# X8-Navboard.net
KiCad netlist of a schematic drawn in EAGLE
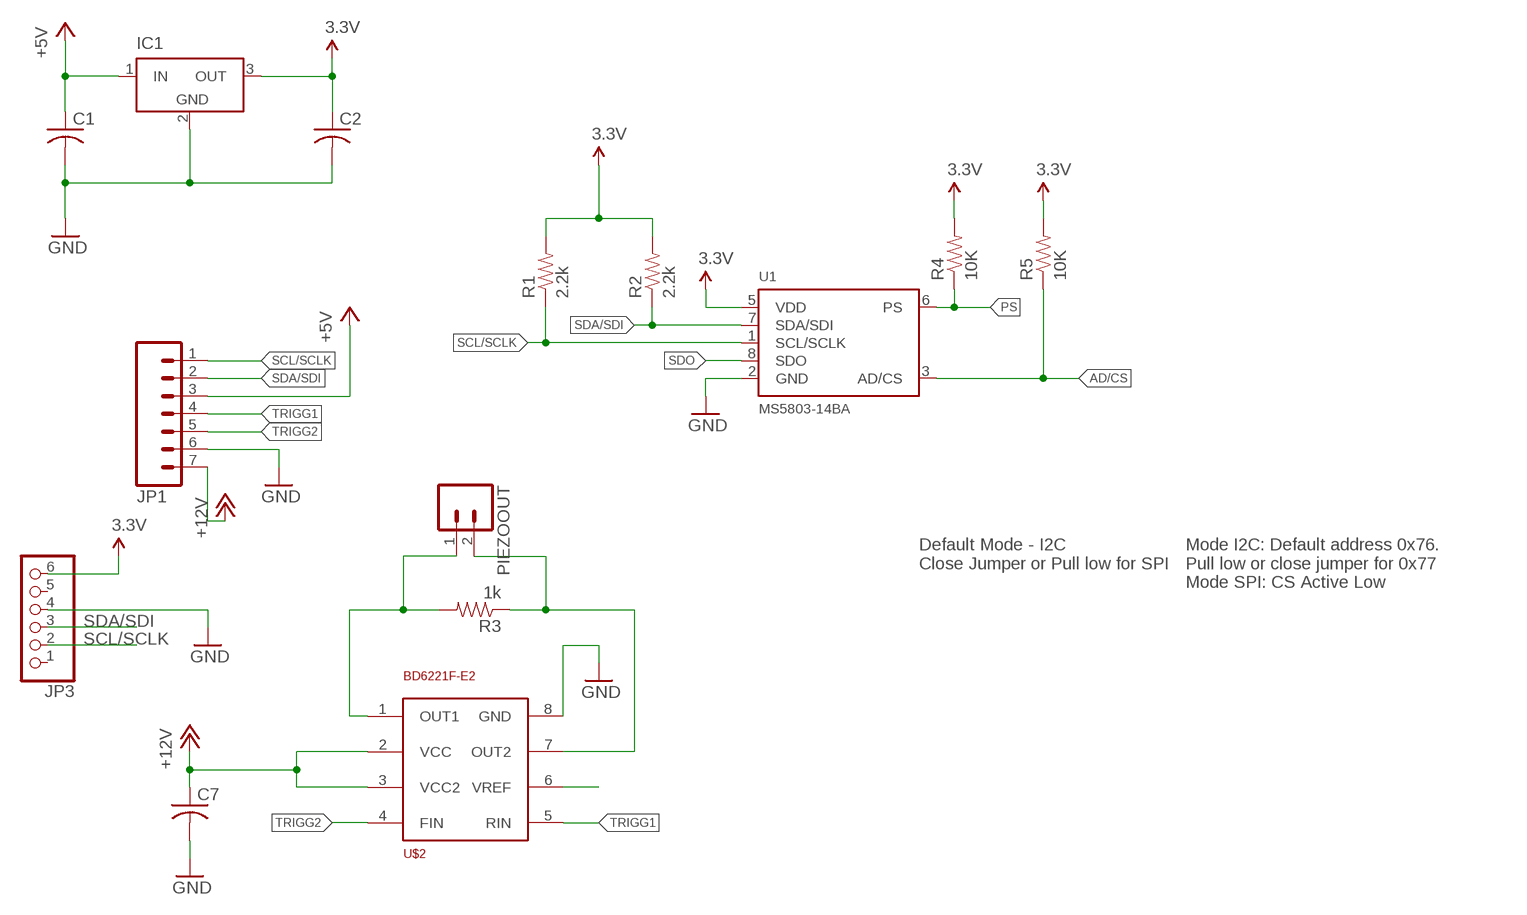
[diagram p0: schematic, sheet 1]

(export (version "E")
  (design (tool "Eeschema 10.0.6"))
  (components
    (comp (ref "C1")
      (value "C-USC0603")
      (footprint "eagle-import:C0603")
      (libsource (lib "eagle-import") (part "C-USC0603"))
    )
    (comp (ref "C2")
      (value "C-USC0603")
      (footprint "eagle-import:C0603")
      (libsource (lib "eagle-import") (part "C-USC0603"))
    )
    (comp (ref "C7")
      (value "C-USC0603")
      (footprint "eagle-import:C0603")
      (libsource (lib "eagle-import") (part "C-USC0603"))
    )
    (comp (ref "IC1")
      (value "LT1129CST5")
      (footprint "eagle-import:SOT223")
      (fields (field (name "MPN") "LT1129CST-5#PBF"))
      (libsource (lib "eagle-import") (part "LT1129CST5"))
    )
    (comp (ref "JP1")
      (value "M07")
      (footprint "eagle-import:1X07")
      (libsource (lib "eagle-import") (part "M07"))
    )
    (comp (ref "JP3")
      (value "PINHD-1X6")
      (footprint "eagle-import:1X06")
      (libsource (lib "eagle-import") (part "PINHD-1X6"))
    )
    (comp (ref "PIEZOOUT")
      (value "M02LOCK_LONGPADS")
      (footprint "eagle-import:1X02_LOCK_LONGPADS")
      (libsource (lib "eagle-import") (part "M02LOCK_LONGPADS"))
    )
    (comp (ref "R1")
      (value "2.2k")
      (footprint "eagle-import:0603-RES")
      (libsource (lib "eagle-import") (part "2.2KOHM1/10W1%(0603)"))
    )
    (comp (ref "R2")
      (value "2.2k")
      (footprint "eagle-import:0603-RES")
      (libsource (lib "eagle-import") (part "2.2KOHM1/10W1%(0603)"))
    )
    (comp (ref "R3")
      (value "1k")
      (footprint "eagle-import:0603-RES")
      (libsource (lib "eagle-import") (part "2.2KOHM1/10W1%(0603)"))
    )
    (comp (ref "R4")
      (value "10K")
      (footprint "eagle-import:0603-RES")
      (libsource (lib "eagle-import") (part "10KOHM1/10W1%(0603)0603"))
    )
    (comp (ref "R5")
      (value "10K")
      (footprint "eagle-import:0603-RES")
      (libsource (lib "eagle-import") (part "10KOHM1/10W1%(0603)0603"))
    )
    (comp (ref "U$2")
      (value "BD6221F-E2")
      (footprint "eagle-import:SOIC8")
      (libsource (lib "eagle-import") (part "BD6221F-E2"))
    )
    (comp (ref "U1")
      (value "MS5803-14BA")
      (footprint "eagle-import:MS5803")
      (libsource (lib "eagle-import") (part "MS5803-14BA"))
    )
  )
  (nets
    (net (code "1") (name "+5V") (class "Default")
      (node (ref "C1") (pin "1") (pinfunction "1_1") (pintype "passive"))
      (node (ref "IC1") (pin "1") (pinfunction "IN_1") (pintype "input"))
      (node (ref "JP1") (pin "3") (pinfunction "3_3") (pintype "passive"))
    )
    (net (code "2") (name "+12V") (class "Default")
      (node (ref "C7") (pin "1") (pinfunction "1_1") (pintype "passive"))
      (node (ref "JP1") (pin "7") (pinfunction "7_7") (pintype "passive"))
      (node (ref "U$2") (pin "2") (pinfunction "VCC_2") (pintype "bidirectional"))
      (node (ref "U$2") (pin "3") (pinfunction "VCC2_3") (pintype "bidirectional"))
    )
    (net (code "3") (name "3.3V") (class "Default")
      (node (ref "C2") (pin "1") (pinfunction "1_1") (pintype "passive"))
      (node (ref "IC1") (pin "3") (pinfunction "OUT_3") (pintype "output"))
      (node (ref "JP3") (pin "6") (pinfunction "6_6") (pintype "passive"))
      (node (ref "R1") (pin "2") (pinfunction "2_2") (pintype "passive"))
      (node (ref "R2") (pin "2") (pinfunction "2_2") (pintype "passive"))
      (node (ref "R4") (pin "2") (pinfunction "2_2") (pintype "passive"))
      (node (ref "R5") (pin "2") (pinfunction "2_2") (pintype "passive"))
      (node (ref "U1") (pin "5") (pinfunction "VDD_5") (pintype "bidirectional"))
    )
    (net (code "4") (name "AD{slash}CS") (class "Default")
      (node (ref "R5") (pin "1") (pinfunction "1_1") (pintype "passive"))
      (node (ref "U1") (pin "3") (pinfunction "AD/CS_3") (pintype "bidirectional"))
    )
    (net (code "5") (name "GND") (class "Default")
      (node (ref "C1") (pin "2") (pinfunction "2_2") (pintype "passive"))
      (node (ref "C2") (pin "2") (pinfunction "2_2") (pintype "passive"))
      (node (ref "C7") (pin "2") (pinfunction "2_2") (pintype "passive"))
      (node (ref "IC1") (pin "2") (pinfunction "GND_2") (pintype "power_in"))
      (node (ref "JP1") (pin "6") (pinfunction "6_6") (pintype "passive"))
      (node (ref "JP3") (pin "4") (pinfunction "4_4") (pintype "passive"))
      (node (ref "U$2") (pin "8") (pinfunction "GND_8") (pintype "bidirectional"))
      (node (ref "U1") (pin "2") (pinfunction "GND_2") (pintype "bidirectional"))
    )
    (net (code "6") (name "Net-(U$2-OUT1)") (class "Default")
      (node (ref "PIEZOOUT") (pin "1") (pinfunction "1_1") (pintype "passive"))
      (node (ref "R3") (pin "2") (pinfunction "2_2") (pintype "passive"))
      (node (ref "U$2") (pin "1") (pinfunction "OUT1_1") (pintype "bidirectional"))
    )
    (net (code "7") (name "Net-(U$2-OUT2)") (class "Default")
      (node (ref "PIEZOOUT") (pin "2") (pinfunction "2_2") (pintype "passive"))
      (node (ref "R3") (pin "1") (pinfunction "1_1") (pintype "passive"))
      (node (ref "U$2") (pin "7") (pinfunction "OUT2_7") (pintype "bidirectional"))
    )
    (net (code "8") (name "PS") (class "Default")
      (node (ref "R4") (pin "1") (pinfunction "1_1") (pintype "passive"))
      (node (ref "U1") (pin "6") (pinfunction "PS_6") (pintype "bidirectional"))
    )
    (net (code "9") (name "SCL{slash}SCLK") (class "Default")
      (node (ref "JP1") (pin "1") (pinfunction "1_1") (pintype "passive"))
      (node (ref "JP3") (pin "2") (pinfunction "2_2") (pintype "passive"))
      (node (ref "R1") (pin "1") (pinfunction "1_1") (pintype "passive"))
      (node (ref "U1") (pin "1") (pinfunction "SCL/SCLK_1") (pintype "bidirectional"))
    )
    (net (code "10") (name "SDA{slash}SDI") (class "Default")
      (node (ref "JP1") (pin "2") (pinfunction "2_2") (pintype "passive"))
      (node (ref "JP3") (pin "3") (pinfunction "3_3") (pintype "passive"))
      (node (ref "R2") (pin "1") (pinfunction "1_1") (pintype "passive"))
      (node (ref "U1") (pin "7") (pinfunction "SDA/SDI_7") (pintype "bidirectional"))
    )
    (net (code "11") (name "SDO") (class "Default")
      (node (ref "U1") (pin "8") (pinfunction "SDO_8") (pintype "bidirectional"))
    )
    (net (code "12") (name "TRIGG1") (class "Default")
      (node (ref "JP1") (pin "4") (pinfunction "4_4") (pintype "passive"))
      (node (ref "U$2") (pin "5") (pinfunction "RIN_5") (pintype "bidirectional"))
    )
    (net (code "13") (name "TRIGG2") (class "Default")
      (node (ref "JP1") (pin "5") (pinfunction "5_5") (pintype "passive"))
      (node (ref "U$2") (pin "4") (pinfunction "FIN_4") (pintype "bidirectional"))
    )
    (net (code "14") (name "unconnected-(JP3-Pad1)") (class "Default")
      (node (ref "JP3") (pin "1") (pinfunction "1_1") (pintype "passive"))
    )
    (net (code "15") (name "unconnected-(JP3-Pad5)") (class "Default")
      (node (ref "JP3") (pin "5") (pinfunction "5_5") (pintype "passive"))
    )
    (net (code "16") (name "unconnected-(U$2-VREF-Pad6)") (class "Default")
      (node (ref "U$2") (pin "6") (pinfunction "VREF_6") (pintype "bidirectional"))
    )
  )
)
